# Output_Connections.net
KiCad netlist of a schematic drawn in Altium Designer
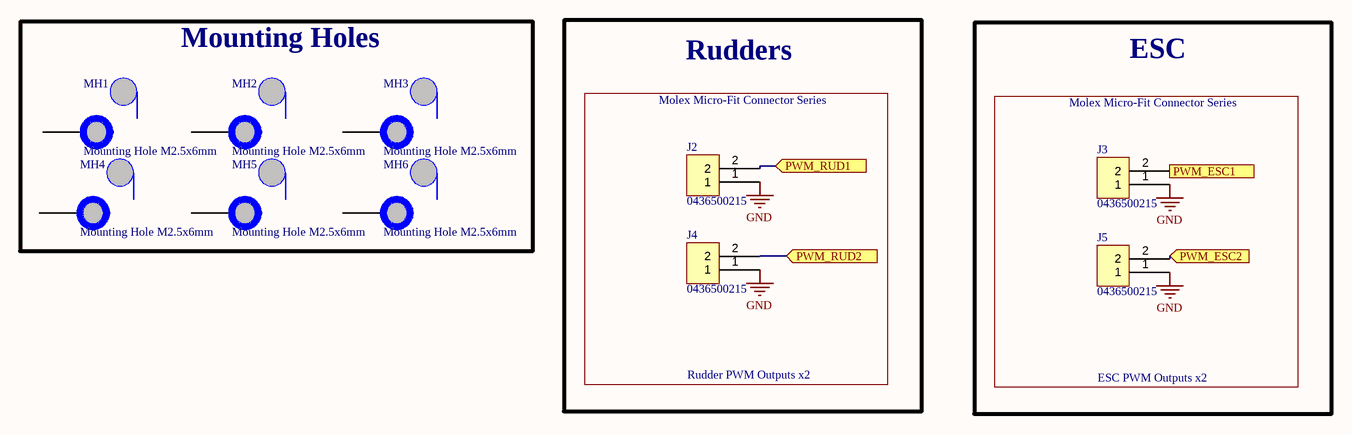
[diagram p0: Output Connections.SchDoc]

(export (version "E")
  (design (tool "Eeschema 10.0.6"))
  (components
    (comp (ref "J2")
      (value "0436500215")
      (footprint "0436500215-Footprint-1")
      (description "Header 1 Row Vertical Polarizing Peg 2 Pin SMT/Glow Wire Compatible Tin Plate")
      (libsource (lib "Americas- Environmental Engineering Club- University of Victoria") (part "0436500215"))
    )
    (comp (ref "J3")
      (value "0436500215")
      (footprint "0436500215-Footprint-1")
      (description "Header 1 Row Vertical Polarizing Peg 2 Pin SMT/Glow Wire Compatible Tin Plate")
      (libsource (lib "Americas- Environmental Engineering Club- University of Victoria") (part "0436500215"))
    )
    (comp (ref "J4")
      (value "0436500215")
      (footprint "0436500215-Footprint-1")
      (description "Header 1 Row Vertical Polarizing Peg 2 Pin SMT/Glow Wire Compatible Tin Plate")
      (libsource (lib "Americas- Environmental Engineering Club- University of Victoria") (part "0436500215"))
    )
    (comp (ref "J5")
      (value "0436500215")
      (footprint "0436500215-Footprint-1")
      (description "Header 1 Row Vertical Polarizing Peg 2 Pin SMT/Glow Wire Compatible Tin Plate")
      (libsource (lib "Americas- Environmental Engineering Club- University of Victoria") (part "0436500215"))
    )
    (comp (ref "MH1")
      (value "Mounting Hole M2.5x6mm")
      (footprint "Mounting Hole M2.5x6mm-Footprint-1")
      (description "M2.5 Mounting Hole")
      (libsource (lib "Americas- Environmental Engineering Club- University of Victoria") (part "Mounting Hole M2.5x6mm-Symbol-1"))
    )
    (comp (ref "MH2")
      (value "Mounting Hole M2.5x6mm")
      (footprint "Mounting Hole M2.5x6mm-Footprint-1")
      (description "M2.5 Mounting Hole")
      (libsource (lib "Americas- Environmental Engineering Club- University of Victoria") (part "Mounting Hole M2.5x6mm-Symbol-1"))
    )
    (comp (ref "MH3")
      (value "Mounting Hole M2.5x6mm")
      (footprint "Mounting Hole M2.5x6mm-Footprint-1")
      (description "M2.5 Mounting Hole")
      (libsource (lib "Americas- Environmental Engineering Club- University of Victoria") (part "Mounting Hole M2.5x6mm-Symbol-1"))
    )
    (comp (ref "MH4")
      (value "Mounting Hole M2.5x6mm")
      (footprint "Mounting Hole M2.5x6mm-Footprint-1")
      (description "M2.5 Mounting Hole")
      (libsource (lib "Americas- Environmental Engineering Club- University of Victoria") (part "Mounting Hole M2.5x6mm-Symbol-1"))
    )
    (comp (ref "MH5")
      (value "Mounting Hole M2.5x6mm")
      (footprint "Mounting Hole M2.5x6mm-Footprint-1")
      (description "M2.5 Mounting Hole")
      (libsource (lib "Americas- Environmental Engineering Club- University of Victoria") (part "Mounting Hole M2.5x6mm-Symbol-1"))
    )
    (comp (ref "MH6")
      (value "Mounting Hole M2.5x6mm")
      (footprint "Mounting Hole M2.5x6mm-Footprint-1")
      (description "M2.5 Mounting Hole")
      (libsource (lib "Americas- Environmental Engineering Club- University of Victoria") (part "Mounting Hole M2.5x6mm-Symbol-1"))
    )
  )
  (nets
    (net (code "1") (name "/PWM_ESC1") (class "Default")
      (node (ref "J3") (pin "2") (pinfunction "2_2") (pintype "power_in"))
    )
    (net (code "2") (name "/PWM_ESC2") (class "Default")
      (node (ref "J5") (pin "2") (pinfunction "2_2") (pintype "power_in"))
    )
    (net (code "3") (name "/PWM_RUD1") (class "Default")
      (node (ref "J2") (pin "2") (pinfunction "2_2") (pintype "power_in"))
    )
    (net (code "4") (name "/PWM_RUD2") (class "Default")
      (node (ref "J4") (pin "2") (pinfunction "2_2") (pintype "power_in"))
    )
    (net (code "5") (name "GND") (class "Default")
      (node (ref "J2") (pin "1") (pinfunction "1_1") (pintype "power_in"))
      (node (ref "J3") (pin "1") (pinfunction "1_1") (pintype "power_in"))
      (node (ref "J4") (pin "1") (pinfunction "1_1") (pintype "power_in"))
      (node (ref "J5") (pin "1") (pinfunction "1_1") (pintype "power_in"))
    )
    (net (code "6") (name "unconnected-(MH1-Pad0)") (class "Default")
      (node (ref "MH1") (pin "0") (pinfunction "0_0") (pintype "passive"))
    )
    (net (code "7") (name "unconnected-(MH2-Pad0)") (class "Default")
      (node (ref "MH2") (pin "0") (pinfunction "0_0") (pintype "passive"))
    )
    (net (code "8") (name "unconnected-(MH3-Pad0)") (class "Default")
      (node (ref "MH3") (pin "0") (pinfunction "0_0") (pintype "passive"))
    )
    (net (code "9") (name "unconnected-(MH4-Pad0)") (class "Default")
      (node (ref "MH4") (pin "0") (pinfunction "0_0") (pintype "passive"))
    )
    (net (code "10") (name "unconnected-(MH5-Pad0)") (class "Default")
      (node (ref "MH5") (pin "0") (pinfunction "0_0") (pintype "passive"))
    )
    (net (code "11") (name "unconnected-(MH6-Pad0)") (class "Default")
      (node (ref "MH6") (pin "0") (pinfunction "0_0") (pintype "passive"))
    )
  )
)
